# SDCARD.net
KiCad netlist of a schematic drawn in Altium Designer
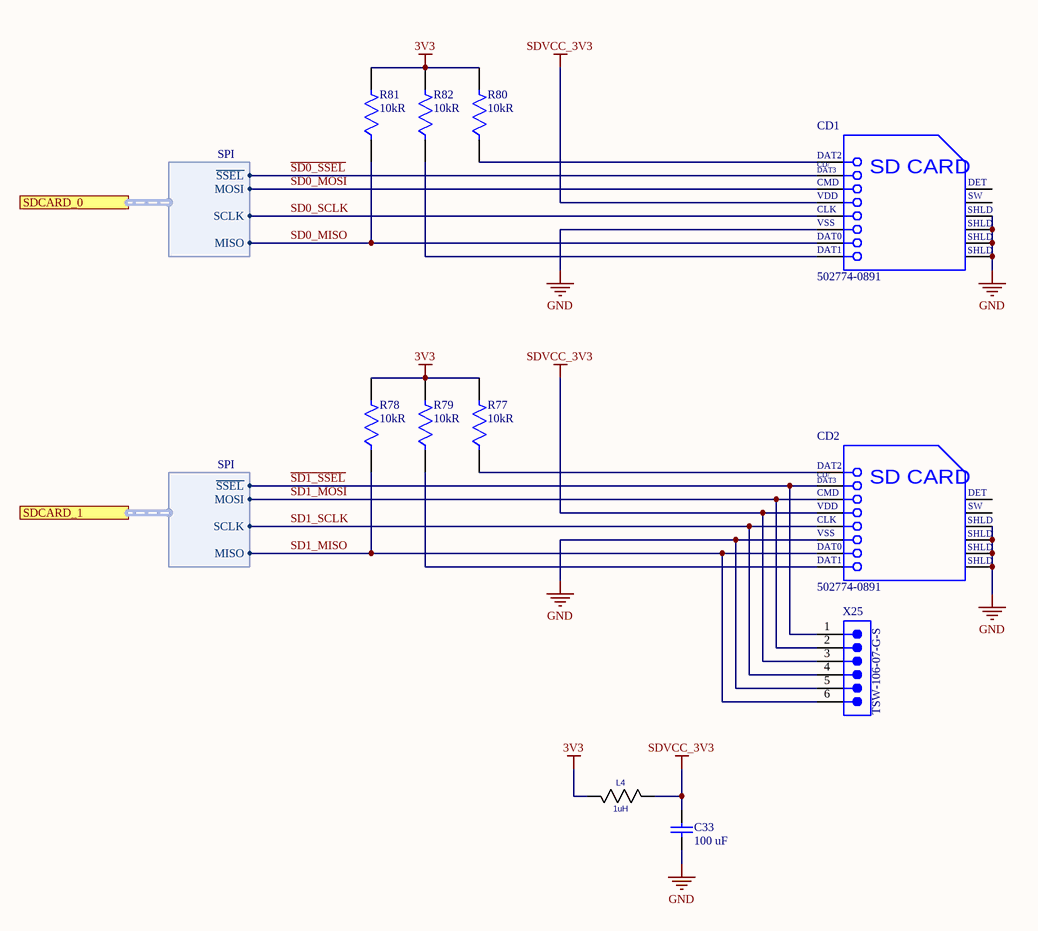
[diagram p0: SDCARD.SchDoc]

(export (version "E")
  (design (tool "Eeschema 10.0.6"))
  (components
    (comp (ref "C33")
      (value "GRM31CR60J107ME39L")
      (footprint "CAPC3216X190X55ML30T25")
      (description "Chip Capacitor, 100 uF, +/- 20%, 6.3 V, -55 to 85 degC, 1206 (3216 Metric), RoHS, Tape and Reel")
      (fields (field (name "CAPACITANCE") "100 uF") (field (name "MANUFACTURER") "Murata"))
      (libsource (lib "zxevo") (part "CMP-1662-00011-2"))
    )
    (comp (ref "CD1")
      (value "502774-0891")
      (footprint "MOLX-502774-0891_V")
      (description "Micro SD Memory Card Connector, 0.5 A, 10 V (DC), -25 to 85 degC, 8-Pin SMT, RoHS, Tape and Reel")
      (fields (field (name "MANUFACTURER") "Molex") (field (name "MANUFACTURER PART NUMBER") "5027740891"))
      (libsource (lib "zxevo") (part "CMP-2000-05248-1"))
    )
    (comp (ref "CD2")
      (value "502774-0891")
      (footprint "MOLX-502774-0891_V")
      (description "Micro SD Memory Card Connector, 0.5 A, 10 V (DC), -25 to 85 degC, 8-Pin SMT, RoHS, Tape and Reel")
      (fields (field (name "MANUFACTURER") "Molex") (field (name "MANUFACTURER PART NUMBER") "5027740891"))
      (libsource (lib "zxevo") (part "CMP-2000-05248-1"))
    )
    (comp (ref "L4")
      (value "1uH")
      (footprint "L-CHIP")
      (description "L-CHIP")
      (libsource (lib "zxevo") (part "L-CHIP"))
    )
    (comp (ref "R77")
      (value "CR0805-JW-103ELF")
      (footprint "FP-CR0805-IPC_A")
      (description "Thick Film Chip Resistors 0805 10kΩ 0.125W 5% 200ppm/°C")
      (fields (field (name "RESISTANCE") "10kR") (field (name "MANUFACTURER") "Bourns"))
      (libsource (lib "zxevo") (part "CMP-07231-003873-1"))
    )
    (comp (ref "R78")
      (value "CR0805-JW-103ELF")
      (footprint "FP-CR0805-IPC_A")
      (description "Thick Film Chip Resistors 0805 10kΩ 0.125W 5% 200ppm/°C")
      (fields (field (name "RESISTANCE") "10kR") (field (name "MANUFACTURER") "Bourns"))
      (libsource (lib "zxevo") (part "CMP-07231-003873-1"))
    )
    (comp (ref "R79")
      (value "CR0805-JW-103ELF")
      (footprint "FP-CR0805-IPC_A")
      (description "Thick Film Chip Resistors 0805 10kΩ 0.125W 5% 200ppm/°C")
      (fields (field (name "RESISTANCE") "10kR") (field (name "MANUFACTURER") "Bourns"))
      (libsource (lib "zxevo") (part "CMP-07231-003873-1"))
    )
    (comp (ref "R80")
      (value "CR0805-JW-103ELF")
      (footprint "FP-CR0805-IPC_A")
      (description "Thick Film Chip Resistors 0805 10kΩ 0.125W 5% 200ppm/°C")
      (fields (field (name "RESISTANCE") "10kR") (field (name "MANUFACTURER") "Bourns"))
      (libsource (lib "zxevo") (part "CMP-07231-003873-1"))
    )
    (comp (ref "R81")
      (value "CR0805-JW-103ELF")
      (footprint "FP-CR0805-IPC_A")
      (description "Thick Film Chip Resistors 0805 10kΩ 0.125W 5% 200ppm/°C")
      (fields (field (name "RESISTANCE") "10kR") (field (name "MANUFACTURER") "Bourns"))
      (libsource (lib "zxevo") (part "CMP-07231-003873-1"))
    )
    (comp (ref "R82")
      (value "CR0805-JW-103ELF")
      (footprint "FP-CR0805-IPC_A")
      (description "Thick Film Chip Resistors 0805 10kΩ 0.125W 5% 200ppm/°C")
      (fields (field (name "RESISTANCE") "10kR") (field (name "MANUFACTURER") "Bourns"))
      (libsource (lib "zxevo") (part "CMP-07231-003873-1"))
    )
    (comp (ref "X25")
      (value "TSW-106-07-G-S")
      (footprint "SMTC-TSW-106-07-X-S")
      (description "0.025\" SQ Post Header, Through-hole, Vertical, -55 to 125 degC, 2.54 mm Pitch, 6-Pin, Male, RoHS")
      (fields (field (name "MANUFACTURER") "Samtec"))
      (libsource (lib "zxevo") (part "CMP-1024-00383-1"))
    )
  )
  (nets
    (net (code "2") (name "/SD0_MISO") (class "Default")
      (node (ref "CD1") (pin "7") (pinfunction "DAT0_7") (pintype "passive"))
      (node (ref "R81") (pin "1") (pinfunction "1_1") (pintype "passive"))
    )
    (net (code "3") (name "/SD0_MOSI") (class "Default")
      (node (ref "CD1") (pin "3") (pinfunction "CMD_3") (pintype "passive"))
    )
    (net (code "4") (name "/SD0_SCLK") (class "Default")
      (node (ref "CD1") (pin "5") (pinfunction "CLK_5") (pintype "passive"))
    )
    (net (code "5") (name "/SD1_MISO") (class "Default")
      (node (ref "CD2") (pin "7") (pinfunction "DAT0_7") (pintype "passive"))
      (node (ref "R78") (pin "1") (pinfunction "1_1") (pintype "passive"))
      (node (ref "X25") (pin "6") (pinfunction "6_6") (pintype "passive"))
    )
    (net (code "6") (name "/SD1_MOSI") (class "Default")
      (node (ref "CD2") (pin "3") (pinfunction "CMD_3") (pintype "passive"))
      (node (ref "X25") (pin "2") (pinfunction "2_2") (pintype "passive"))
    )
    (net (code "7") (name "/SD1_SCLK") (class "Default")
      (node (ref "CD2") (pin "5") (pinfunction "CLK_5") (pintype "passive"))
      (node (ref "X25") (pin "4") (pinfunction "4_4") (pintype "passive"))
    )
    (net (code "9") (name "/~{SD0_SSEL}") (class "Default")
      (node (ref "CD1") (pin "2") (pinfunction "CD/DAT3_2") (pintype "passive"))
    )
    (net (code "10") (name "/~{SD1_SSEL}") (class "Default")
      (node (ref "CD2") (pin "2") (pinfunction "CD/DAT3_2") (pintype "passive"))
      (node (ref "X25") (pin "1") (pinfunction "1_1") (pintype "passive"))
    )
    (net (code "11") (name "3V3") (class "Default")
      (node (ref "L4") (pin "2") (pintype "passive"))
      (node (ref "R77") (pin "2") (pinfunction "2_2") (pintype "passive"))
      (node (ref "R78") (pin "2") (pinfunction "2_2") (pintype "passive"))
      (node (ref "R79") (pin "2") (pinfunction "2_2") (pintype "passive"))
      (node (ref "R80") (pin "2") (pinfunction "2_2") (pintype "passive"))
      (node (ref "R81") (pin "2") (pinfunction "2_2") (pintype "passive"))
      (node (ref "R82") (pin "2") (pinfunction "2_2") (pintype "passive"))
    )
    (net (code "12") (name "GND") (class "Default")
      (node (ref "C33") (pin "1") (pinfunction "1_1") (pintype "passive"))
      (node (ref "CD1") (pin "11") (pinfunction "SHLD_11") (pintype "passive"))
      (node (ref "CD1") (pin "12") (pinfunction "SHLD_12") (pintype "passive"))
      (node (ref "CD1") (pin "13") (pinfunction "SHLD_13") (pintype "passive"))
      (node (ref "CD1") (pin "14") (pinfunction "SHLD_14") (pintype "passive"))
      (node (ref "CD1") (pin "6") (pinfunction "VSS_6") (pintype "passive"))
      (node (ref "CD2") (pin "11") (pinfunction "SHLD_11") (pintype "passive"))
      (node (ref "CD2") (pin "12") (pinfunction "SHLD_12") (pintype "passive"))
      (node (ref "CD2") (pin "13") (pinfunction "SHLD_13") (pintype "passive"))
      (node (ref "CD2") (pin "14") (pinfunction "SHLD_14") (pintype "passive"))
      (node (ref "CD2") (pin "6") (pinfunction "VSS_6") (pintype "passive"))
      (node (ref "X25") (pin "5") (pinfunction "5_5") (pintype "passive"))
    )
    (net (code "13") (name "Net-(CD1-DAT1)") (class "Default")
      (node (ref "CD1") (pin "8") (pinfunction "DAT1_8") (pintype "passive"))
      (node (ref "R82") (pin "1") (pinfunction "1_1") (pintype "passive"))
    )
    (net (code "14") (name "Net-(CD1-DAT2)") (class "Default")
      (node (ref "CD1") (pin "1") (pinfunction "DAT2_1") (pintype "passive"))
      (node (ref "R80") (pin "1") (pinfunction "1_1") (pintype "passive"))
    )
    (net (code "15") (name "Net-(CD2-DAT1)") (class "Default")
      (node (ref "CD2") (pin "8") (pinfunction "DAT1_8") (pintype "passive"))
      (node (ref "R79") (pin "1") (pinfunction "1_1") (pintype "passive"))
    )
    (net (code "16") (name "Net-(CD2-DAT2)") (class "Default")
      (node (ref "CD2") (pin "1") (pinfunction "DAT2_1") (pintype "passive"))
      (node (ref "R77") (pin "1") (pinfunction "1_1") (pintype "passive"))
    )
    (net (code "17") (name "SDVCC_3V3") (class "Default")
      (node (ref "C33") (pin "2") (pinfunction "2_2") (pintype "passive"))
      (node (ref "CD1") (pin "4") (pinfunction "VDD_4") (pintype "passive"))
      (node (ref "CD2") (pin "4") (pinfunction "VDD_4") (pintype "passive"))
      (node (ref "L4") (pin "1") (pintype "passive"))
      (node (ref "X25") (pin "3") (pinfunction "3_3") (pintype "passive"))
    )
    (net (code "18") (name "unconnected-(CD1-DETECT-Pad9)") (class "Default")
      (node (ref "CD1") (pin "9") (pinfunction "DETECT_9") (pintype "passive"))
    )
    (net (code "19") (name "unconnected-(CD1-SWITCH-Pad10)") (class "Default")
      (node (ref "CD1") (pin "10") (pinfunction "SWITCH_10") (pintype "passive"))
    )
    (net (code "20") (name "unconnected-(CD2-DETECT-Pad9)") (class "Default")
      (node (ref "CD2") (pin "9") (pinfunction "DETECT_9") (pintype "passive"))
    )
    (net (code "21") (name "unconnected-(CD2-SWITCH-Pad10)") (class "Default")
      (node (ref "CD2") (pin "10") (pinfunction "SWITCH_10") (pintype "passive"))
    )
  )
)
